# KUBODriver_MCU.net
KiCad netlist of a schematic drawn in Altium Designer
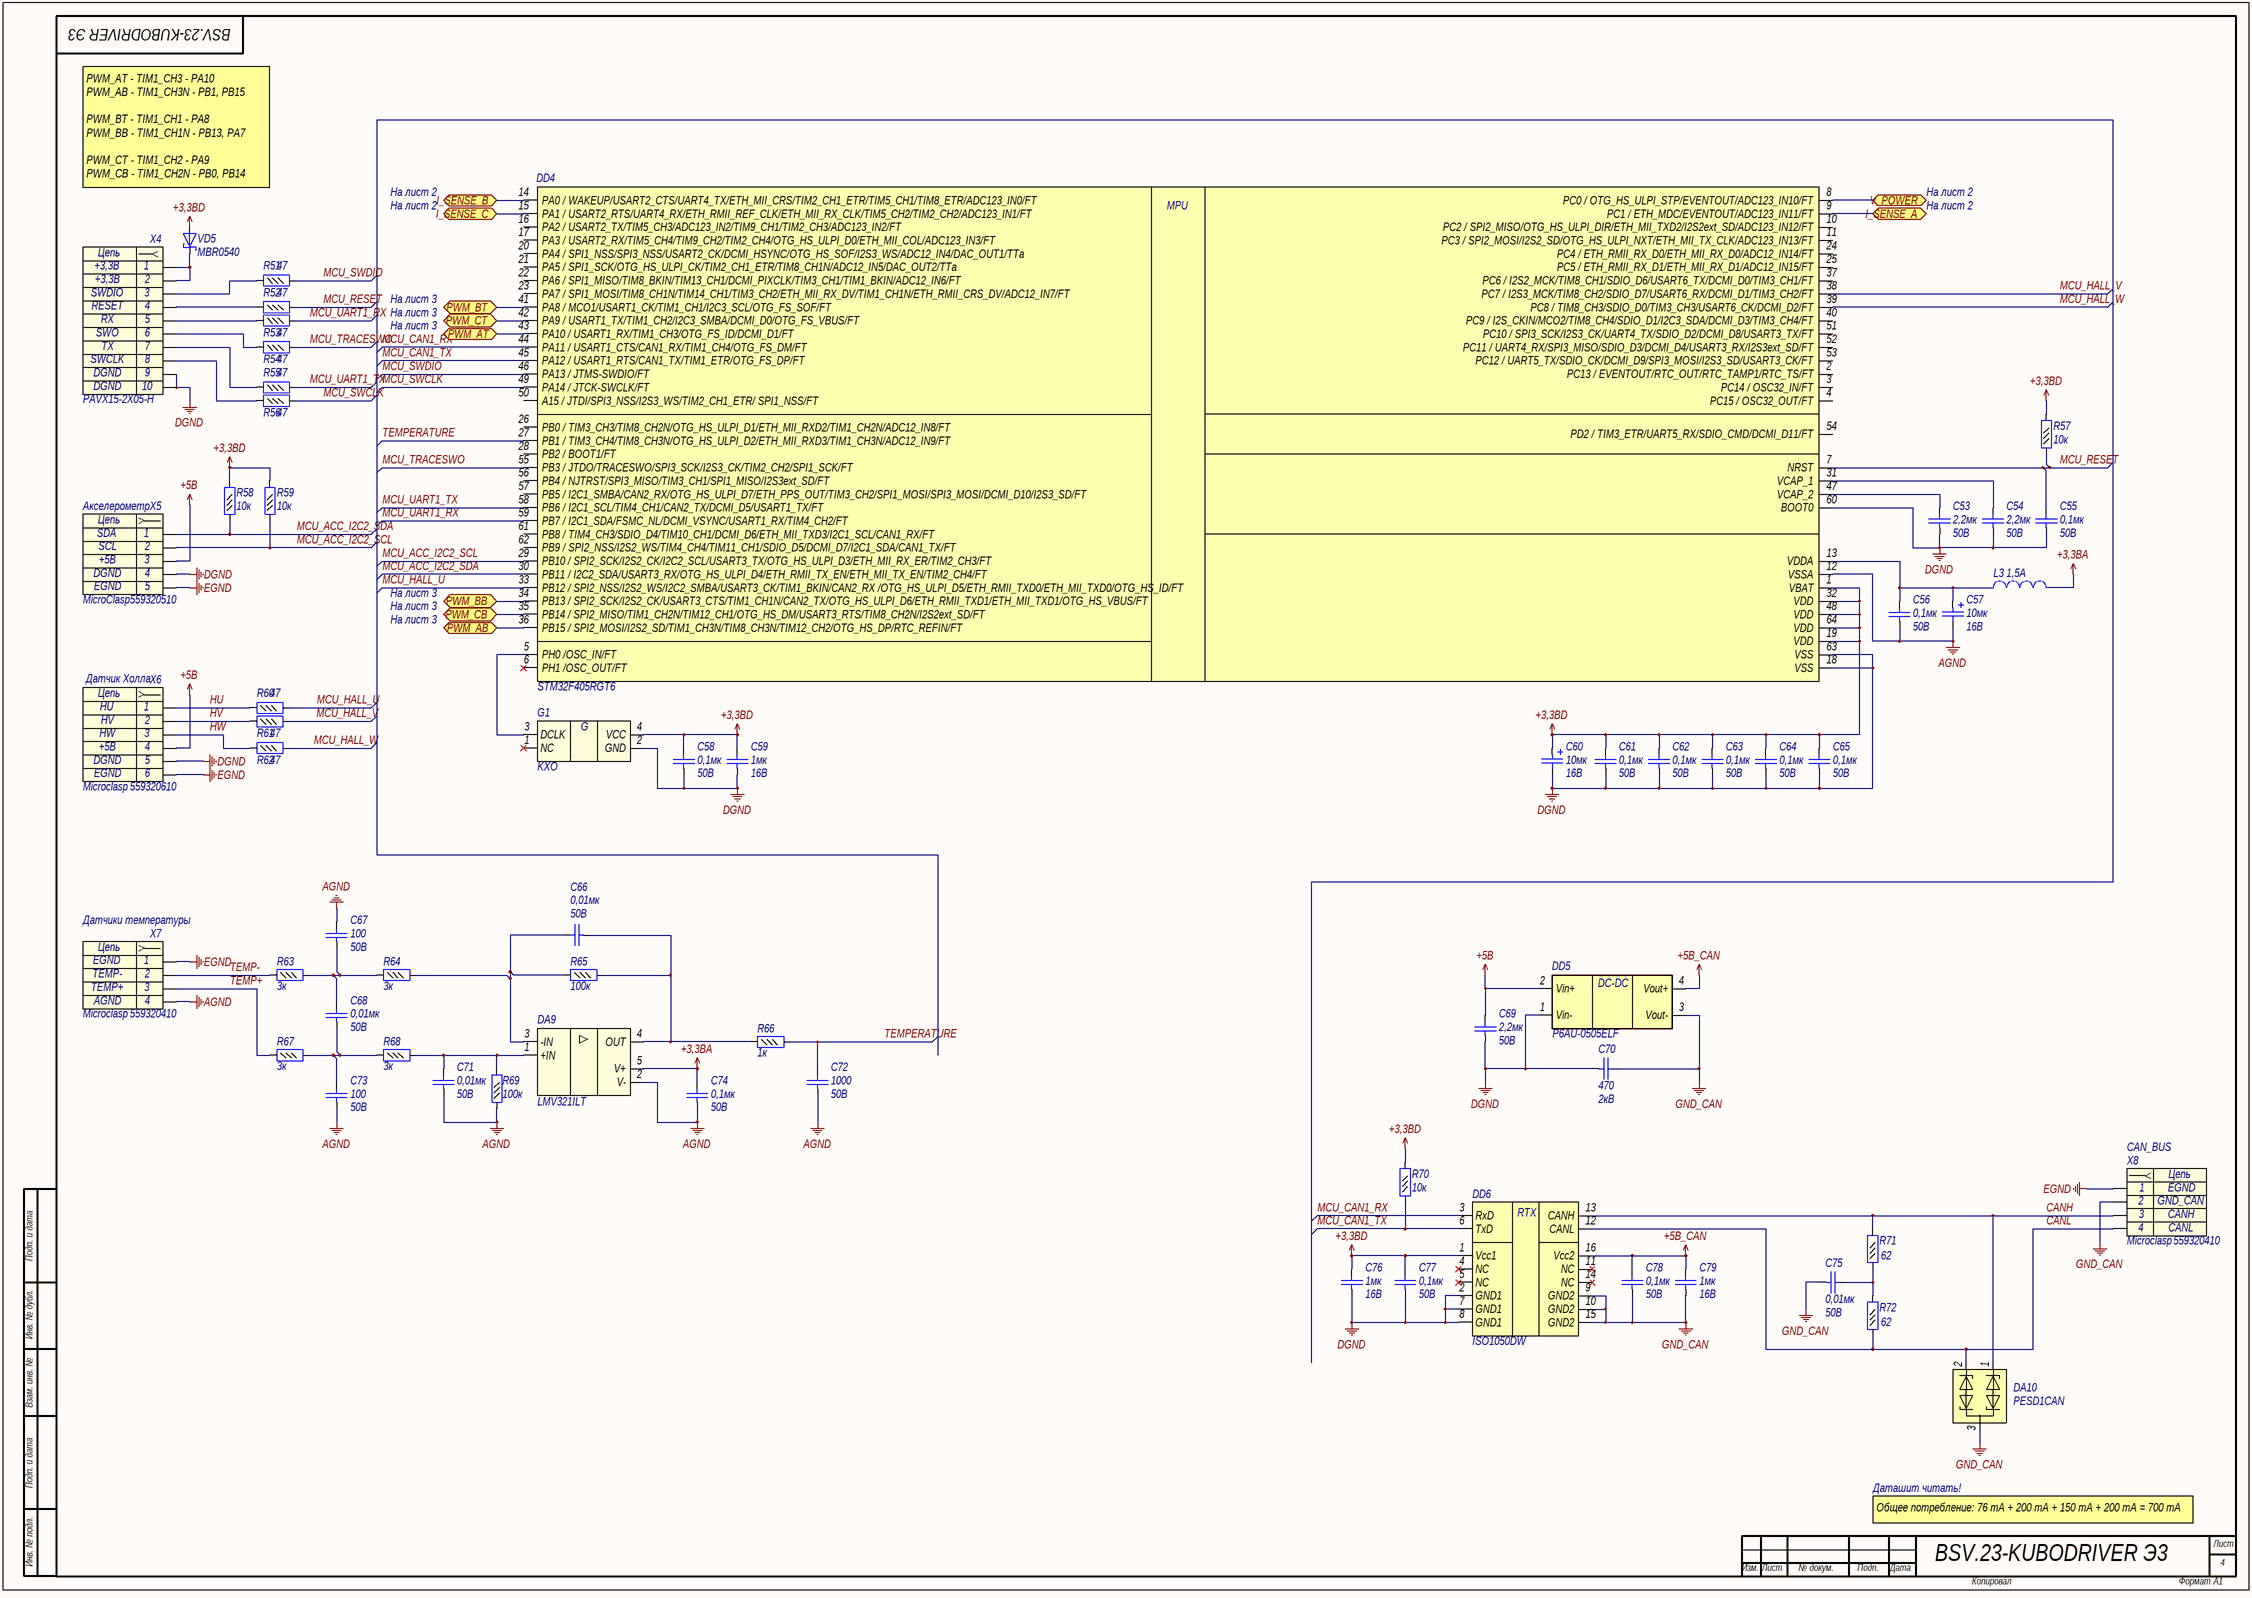
[diagram p0: KUBODriver_MCU.SchDoc]

(export (version "E")
  (design (tool "Eeschema 10.0.6"))
  (components
    (comp (ref "C53")
      (value "2,2мк")
      (footprint "C0603")
      (description "Конденсатор")
      (fields
        (field (name "VOLTAGE") "50B")
        (field (name "PART NUMBER") "GRM188R71A225KE15D")
        (field (name "Comment") "Capacitor")
      )
      (libsource (lib "MOP44") (part "Capacitor"))
    )
    (comp (ref "C54")
      (value "2,2мк")
      (footprint "C0603")
      (description "Конденсатор")
      (fields
        (field (name "VOLTAGE") "50B")
        (field (name "PART NUMBER") "GRM188R71A225KE15D")
        (field (name "Comment") "Capacitor")
      )
      (libsource (lib "MOP44") (part "Capacitor"))
    )
    (comp (ref "C55")
      (value "0,1мк")
      (footprint "C0402")
      (description "Конденсатор")
      (fields
        (field (name "VOLTAGE") "50В")
        (field (name "PART NUMBER") "GRM155R71H104KE14D ")
        (field (name "Comment") "Capacitor")
      )
      (libsource (lib "MOP44") (part "Capacitor"))
    )
    (comp (ref "C56")
      (value "0,1мк")
      (footprint "C0402")
      (description "Конденсатор")
      (fields
        (field (name "VOLTAGE") "50В")
        (field (name "PART NUMBER") "GRM155R71H104KE14D ")
        (field (name "Comment") "Capacitor")
      )
      (libsource (lib "MOP44") (part "Capacitor"))
    )
    (comp (ref "C57")
      (value "10мк")
      (footprint "TANTAL CASE A")
      (description "Конденсатор полярный")
      (fields
        (field (name "VOLTAGE") "16В")
        (field (name "PART NUMBER") "293D106X9016A2TE3")
        (field (name "Comment") "Capacitor_pol")
      )
      (libsource (lib "MOP44") (part "Capacitor_pol"))
    )
    (comp (ref "C58")
      (value "0,1мк")
      (footprint "C0402")
      (description "Конденсатор")
      (fields
        (field (name "VOLTAGE") "50В")
        (field (name "PART NUMBER") "GRM155R71H104KE14D ")
        (field (name "Comment") "Capacitor")
      )
      (libsource (lib "MOP44") (part "Capacitor"))
    )
    (comp (ref "C59")
      (value "1мк")
      (footprint "C0603")
      (description "Конденсатор")
      (fields
        (field (name "VOLTAGE") "16B")
        (field (name "PART NUMBER") "GRM188R71C105KA12D**")
        (field (name "Comment") "Capacitor")
      )
      (libsource (lib "MOP44") (part "Capacitor"))
    )
    (comp (ref "C60")
      (value "10мк")
      (footprint "TANTAL CASE A")
      (description "Конденсатор полярный")
      (fields
        (field (name "VOLTAGE") "16В")
        (field (name "PART NUMBER") "293D106X9016A2TE3")
        (field (name "Comment") "Capacitor_pol")
      )
      (libsource (lib "MOP44") (part "Capacitor_pol"))
    )
    (comp (ref "C61")
      (value "0,1мк")
      (footprint "C0402")
      (description "Конденсатор")
      (fields
        (field (name "VOLTAGE") "50В")
        (field (name "PART NUMBER") "GRM155R71H104KE14D ")
        (field (name "Comment") "Capacitor")
      )
      (libsource (lib "MOP44") (part "Capacitor"))
    )
    (comp (ref "C62")
      (value "0,1мк")
      (footprint "C0402")
      (description "Конденсатор")
      (fields
        (field (name "VOLTAGE") "50В")
        (field (name "PART NUMBER") "GRM155R71H104KE14D ")
        (field (name "Comment") "Capacitor")
      )
      (libsource (lib "MOP44") (part "Capacitor"))
    )
    (comp (ref "C63")
      (value "0,1мк")
      (footprint "C0402")
      (description "Конденсатор")
      (fields
        (field (name "VOLTAGE") "50В")
        (field (name "PART NUMBER") "GRM155R71H104KE14D ")
        (field (name "Comment") "Capacitor")
      )
      (libsource (lib "MOP44") (part "Capacitor"))
    )
    (comp (ref "C64")
      (value "0,1мк")
      (footprint "C0402")
      (description "Конденсатор")
      (fields
        (field (name "VOLTAGE") "50В")
        (field (name "PART NUMBER") "GRM155R71H104KE14D ")
        (field (name "Comment") "Capacitor")
      )
      (libsource (lib "MOP44") (part "Capacitor"))
    )
    (comp (ref "C65")
      (value "0,1мк")
      (footprint "C0402")
      (description "Конденсатор")
      (fields
        (field (name "VOLTAGE") "50В")
        (field (name "PART NUMBER") "GRM155R71H104KE14D ")
        (field (name "Comment") "Capacitor")
      )
      (libsource (lib "MOP44") (part "Capacitor"))
    )
    (comp (ref "C66")
      (value "0,01мк")
      (footprint "C0402")
      (description "Конденсатор")
      (fields
        (field (name "VOLTAGE") "50B")
        (field (name "PART NUMBER") "GRM155R71H103K")
        (field (name "Comment") "Capacitor")
      )
      (libsource (lib "MOP44") (part "Capacitor"))
    )
    (comp (ref "C67")
      (value "100")
      (footprint "C0402")
      (description "Конденсатор")
      (fields
        (field (name "VOLTAGE") "50B")
        (field (name "PART NUMBER") "GRM1535C1H101J")
        (field (name "Comment") "Capacitor")
      )
      (libsource (lib "MOP44") (part "Capacitor"))
    )
    (comp (ref "C68")
      (value "0,01мк")
      (footprint "C0402")
      (description "Конденсатор")
      (fields
        (field (name "VOLTAGE") "50B")
        (field (name "PART NUMBER") "GRM155R71H103K")
        (field (name "Comment") "Capacitor")
      )
      (libsource (lib "MOP44") (part "Capacitor"))
    )
    (comp (ref "C69")
      (value "2,2мк")
      (footprint "C0603")
      (description "Конденсатор")
      (fields
        (field (name "VOLTAGE") "50B")
        (field (name "PART NUMBER") "GRM188R71A225KE15D")
        (field (name "Comment") "Capacitor")
      )
      (libsource (lib "MOP44") (part "Capacitor"))
    )
    (comp (ref "C70")
      (value "470")
      (footprint "C1206")
      (description "Конденсатор")
      (fields
        (field (name "VOLTAGE") "2кВ")
        (field (name "PART NUMBER") "CC1206KKX7RDBB471 ")
        (field (name "Comment") "Capacitor")
      )
      (libsource (lib "MOP44") (part "Capacitor"))
    )
    (comp (ref "C71")
      (value "0,01мк")
      (footprint "C0402")
      (description "Конденсатор")
      (fields
        (field (name "VOLTAGE") "50B")
        (field (name "PART NUMBER") "GRM155R71H103K")
        (field (name "Comment") "Capacitor")
      )
      (libsource (lib "MOP44") (part "Capacitor"))
    )
    (comp (ref "C72")
      (value "1000")
      (footprint "C0402")
      (description "Конденсатор")
      (fields
        (field (name "VOLTAGE") "50B")
        (field (name "PART NUMBER") "GRM1555C1H102J")
        (field (name "Comment") "Capacitor")
      )
      (libsource (lib "MOP44") (part "Capacitor"))
    )
    (comp (ref "C73")
      (value "100")
      (footprint "C0402")
      (description "Конденсатор")
      (fields
        (field (name "VOLTAGE") "50B")
        (field (name "PART NUMBER") "GRM1535C1H101J")
        (field (name "Comment") "Capacitor")
      )
      (libsource (lib "MOP44") (part "Capacitor"))
    )
    (comp (ref "C74")
      (value "0,1мк")
      (footprint "C0402")
      (description "Конденсатор")
      (fields
        (field (name "VOLTAGE") "50В")
        (field (name "PART NUMBER") "GRM155R71H104KE14D ")
        (field (name "Comment") "Capacitor")
      )
      (libsource (lib "MOP44") (part "Capacitor"))
    )
    (comp (ref "C75")
      (value "0,01мк")
      (footprint "C0402")
      (description "Конденсатор")
      (fields
        (field (name "VOLTAGE") "50B")
        (field (name "PART NUMBER") "GRM155R71H103K")
        (field (name "Comment") "Capacitor")
      )
      (libsource (lib "MOP44") (part "Capacitor"))
    )
    (comp (ref "C76")
      (value "1мк")
      (footprint "C0603")
      (description "Конденсатор")
      (fields
        (field (name "VOLTAGE") "16B")
        (field (name "PART NUMBER") "GRM188R71C105KA12D**")
        (field (name "Comment") "Capacitor")
      )
      (libsource (lib "MOP44") (part "Capacitor"))
    )
    (comp (ref "C77")
      (value "0,1мк")
      (footprint "C0402")
      (description "Конденсатор")
      (fields
        (field (name "VOLTAGE") "50В")
        (field (name "PART NUMBER") "GRM155R71H104KE14D ")
        (field (name "Comment") "Capacitor")
      )
      (libsource (lib "MOP44") (part "Capacitor"))
    )
    (comp (ref "C78")
      (value "0,1мк")
      (footprint "C0402")
      (description "Конденсатор")
      (fields
        (field (name "VOLTAGE") "50В")
        (field (name "PART NUMBER") "GRM155R71H104KE14D ")
        (field (name "Comment") "Capacitor")
      )
      (libsource (lib "MOP44") (part "Capacitor"))
    )
    (comp (ref "C79")
      (value "1мк")
      (footprint "C0603")
      (description "Конденсатор")
      (fields
        (field (name "VOLTAGE") "16B")
        (field (name "PART NUMBER") "GRM188R71C105KA12D**")
        (field (name "Comment") "Capacitor")
      )
      (libsource (lib "MOP44") (part "Capacitor"))
    )
    (comp (ref "DA9")
      (value "LMV321ILT")
      (footprint "SOT23-5")
      (description "HIGH-DRIVE OPERATIONAL AMPLIFIERS WITH SHUTDOWN")
      (libsource (lib "MOP44") (part "LMV321ILT"))
    )
    (comp (ref "DA10")
      (value "PESD")
      (footprint "SOT23-3")
      (description "TVS")
      (fields (field (name "PART NUMBER") "PESD1CAN"))
      (libsource (lib "MOP44") (part "PESD"))
    )
    (comp (ref "DD4")
      (value "STM32F405RGT6")
      (footprint "LQFP64")
      (libsource (lib "MOP44") (part "STM32F405RGT6"))
    )
    (comp (ref "DD5")
      (value "P6AU-xxxxELF")
      (footprint "SIP4")
      (description "DC/DC преобразователь")
      (fields (field (name "PART NUMBER") "P6AU-0505ELF") (field (name "MANUFACTURER") "PEAK Electronics"))
      (libsource (lib "MOP44") (part "P6AU-xxxxELF"))
    )
    (comp (ref "DD6")
      (value "~")
      (footprint "SO16")
      (description "Isolated CAN Transceiver")
      (fields (field (name "PART NUMBER") "ISO1050DW"))
      (libsource (lib "MOP44") (part "ISO1050DW"))
    )
    (comp (ref "G1")
      (value "KXO")
      (footprint "QSMD7x5.2x1.8")
      (description "Кварц. генер. 32.768 МГц (HCMOS/TTL)")
      (fields (field (name "PART NUMBER") "KXO-V97"))
      (libsource (lib "MOP44") (part "KXO"))
    )
    (comp (ref "L3")
      (value "Inductor")
      (footprint "L0603")
      (description "EMI Suppression Filter")
      (fields (field (name "RATED CURRENT") "1,5A") (field (name "PART NUMBER") "BLM18PG181SN1D"))
      (libsource (lib "MOP44") (part "Inductor"))
    )
    (comp (ref "R51")
      (value "47")
      (footprint "R0402")
      (description "Резистор")
      (fields (field (name "PART NUMBER") "RC0402FR-0747RL") (field (name "POWER") "0,062Вт"))
      (libsource (lib "MOP44") (part "Resistor_0,062Вт"))
    )
    (comp (ref "R52")
      (value "47")
      (footprint "R0402")
      (description "Резистор")
      (fields (field (name "PART NUMBER") "RC0402FR-0747RL") (field (name "POWER") "0,062Вт"))
      (libsource (lib "MOP44") (part "Resistor_0,062Вт"))
    )
    (comp (ref "R53")
      (value "47")
      (footprint "R0402")
      (description "Резистор")
      (fields (field (name "PART NUMBER") "RC0402FR-0747RL") (field (name "POWER") "0,062Вт"))
      (libsource (lib "MOP44") (part "Resistor_0,062Вт"))
    )
    (comp (ref "R54")
      (value "47")
      (footprint "R0402")
      (description "Резистор")
      (fields (field (name "PART NUMBER") "RC0402FR-0747RL") (field (name "POWER") "0,062Вт"))
      (libsource (lib "MOP44") (part "Resistor_0,062Вт"))
    )
    (comp (ref "R55")
      (value "47")
      (footprint "R0402")
      (description "Резистор")
      (fields (field (name "PART NUMBER") "RC0402FR-0747RL") (field (name "POWER") "0,062Вт"))
      (libsource (lib "MOP44") (part "Resistor_0,062Вт"))
    )
    (comp (ref "R56")
      (value "47")
      (footprint "R0402")
      (description "Резистор")
      (fields (field (name "PART NUMBER") "RC0402FR-0747RL") (field (name "POWER") "0,062Вт"))
      (libsource (lib "MOP44") (part "Resistor_0,062Вт"))
    )
    (comp (ref "R57")
      (value "10к")
      (footprint "R0402")
      (description "Резистор")
      (fields (field (name "PART NUMBER") "RC0402FR-0710KL") (field (name "POWER") "0,062Вт"))
      (libsource (lib "") (part "Resistor_0,062Вт_1"))
    )
    (comp (ref "R58")
      (value "10к")
      (footprint "R0402")
      (description "Резистор")
      (fields (field (name "PART NUMBER") "RC0402FR-0710KL") (field (name "POWER") "0,062Вт"))
      (libsource (lib "") (part "Resistor_0,062Вт_1"))
    )
    (comp (ref "R59")
      (value "10к")
      (footprint "R0402")
      (description "Резистор")
      (fields (field (name "PART NUMBER") "RC0402FR-0710KL") (field (name "POWER") "0,062Вт"))
      (libsource (lib "") (part "Resistor_0,062Вт_1"))
    )
    (comp (ref "R60")
      (value "47")
      (footprint "R0402")
      (description "Резистор")
      (fields (field (name "PART NUMBER") "RC0402FR-0747RL") (field (name "POWER") "0,062Вт"))
      (libsource (lib "MOP44") (part "Resistor_0,062Вт"))
    )
    (comp (ref "R61")
      (value "47")
      (footprint "R0402")
      (description "Резистор")
      (fields (field (name "PART NUMBER") "RC0402FR-0747RL") (field (name "POWER") "0,062Вт"))
      (libsource (lib "MOP44") (part "Resistor_0,062Вт"))
    )
    (comp (ref "R62")
      (value "47")
      (footprint "R0402")
      (description "Резистор")
      (fields (field (name "PART NUMBER") "RC0402FR-0747RL") (field (name "POWER") "0,062Вт"))
      (libsource (lib "MOP44") (part "Resistor_0,062Вт"))
    )
    (comp (ref "R63")
      (value "3к")
      (footprint "R0402")
      (description "Резистор")
      (fields (field (name "PART NUMBER") "RC0402FR-073KL") (field (name "POWER") "0,062Вт"))
      (libsource (lib "MOP44") (part "Resistor_0,062Вт"))
    )
    (comp (ref "R64")
      (value "3к")
      (footprint "R0402")
      (description "Резистор")
      (fields (field (name "PART NUMBER") "RC0402FR-073KL") (field (name "POWER") "0,062Вт"))
      (libsource (lib "MOP44") (part "Resistor_0,062Вт"))
    )
    (comp (ref "R65")
      (value "100к")
      (footprint "R0402")
      (description "Резистор")
      (fields (field (name "PART NUMBER") "RC0402FR-07100KL") (field (name "POWER") "0,062Вт"))
      (libsource (lib "MOP44") (part "Resistor_0,062Вт"))
    )
    (comp (ref "R66")
      (value "1к")
      (footprint "R0402")
      (description "Резистор")
      (fields (field (name "PART NUMBER") "RC0402FR-071KL") (field (name "POWER") "0,062Вт"))
      (libsource (lib "MOP44") (part "Resistor_0,062Вт"))
    )
    (comp (ref "R67")
      (value "3к")
      (footprint "R0402")
      (description "Резистор")
      (fields (field (name "PART NUMBER") "RC0402FR-073KL") (field (name "POWER") "0,062Вт"))
      (libsource (lib "MOP44") (part "Resistor_0,062Вт"))
    )
    (comp (ref "R68")
      (value "3к")
      (footprint "R0402")
      (description "Резистор")
      (fields (field (name "PART NUMBER") "RC0402FR-073KL") (field (name "POWER") "0,062Вт"))
      (libsource (lib "MOP44") (part "Resistor_0,062Вт"))
    )
    (comp (ref "R69")
      (value "100к")
      (footprint "R0402")
      (description "Резистор")
      (fields (field (name "PART NUMBER") "RC0402FR-07100KL") (field (name "POWER") "0,062Вт"))
      (libsource (lib "") (part "Resistor_0,062Вт_1"))
    )
    (comp (ref "R70")
      (value "10к")
      (footprint "R0402")
      (description "Резистор")
      (fields (field (name "PART NUMBER") "RC0402FR-0710KL") (field (name "POWER") "0,062Вт"))
      (libsource (lib "") (part "Resistor_0,062Вт_1"))
    )
    (comp (ref "R71")
      (value "62")
      (footprint "R0402")
      (description "Резистор")
      (fields (field (name "PART NUMBER") "RC0402FR-0762RL") (field (name "POWER") "0,062Вт"))
      (libsource (lib "") (part "Resistor_0,062Вт_1"))
    )
    (comp (ref "R72")
      (value "62")
      (footprint "R0402")
      (description "Резистор")
      (fields (field (name "PART NUMBER") "RC0402FR-0762RL") (field (name "POWER") "0,062Вт"))
      (libsource (lib "") (part "Resistor_0,062Вт_1"))
    )
    (comp (ref "VD5")
      (value "DiodeSchottky")
      (footprint "SOD-123")
      (description "Диод Шоттки")
      (fields (field (name "PART NUMBER") "MBR0540"))
      (libsource (lib "MOP44") (part "DiodeSchottky"))
    )
    (comp (ref "X4")
      (value "Header_10_sct")
      (footprint "PAVX15-2X05-H")
      (description "Разъем - 10 конт. розетка")
      (fields (field (name "PART NUMBER") "PAVX15-2X05-H"))
      (libsource (lib "MOP44") (part "Header_10_sct"))
    )
    (comp (ref "X5")
      (value "Акселерометр")
      (footprint "MOLEX_559320510")
      (description "Разъем - 5 конт. розетка")
      (fields (field (name "PART NAME") "MicroClasp") (field (name "PART NUMBER") "559320510"))
      (libsource (lib "MOP44") (part "Header_5_sct"))
    )
    (comp (ref "X6")
      (value "Датчик Холла")
      (footprint "MOLEX_559320610")
      (description "Разъем - 6 конт. розетка")
      (fields (field (name "PART NUMBER") "559320610"))
      (libsource (lib "MOP44") (part "Header_6_sct"))
    )
    (comp (ref "X7")
      (value "Датчики температуры")
      (footprint "MOLEX_559320410")
      (description "Разъем - 4 конт. розетка")
      (fields (field (name "PART NUMBER") "559320410"))
      (libsource (lib "") (part "Header_4_sct_1"))
    )
    (comp (ref "X8")
      (value "CAN_BUS")
      (footprint "MOLEX_559320410")
      (description "Разъем - 4 конт. розетка")
      (fields (field (name "PART NUMBER") "559320410"))
      (libsource (lib "MOP44") (part "Header_4_sct"))
    )
  )
  (nets
    (net (code "1") (name "+3,3BA") (class "Default")
      (node (ref "C74") (pin "2") (pinfunction "2_2") (pintype "passive"))
      (node (ref "DA9") (pin "5") (pinfunction "V+_5") (pintype "passive"))
      (node (ref "L3") (pin "2") (pinfunction "2_2") (pintype "passive"))
    )
    (net (code "2") (name "+3,3BD") (class "Default")
      (node (ref "C58") (pin "2") (pinfunction "2_2") (pintype "passive"))
      (node (ref "C59") (pin "2") (pinfunction "2_2") (pintype "passive"))
      (node (ref "C60") (pin "1") (pinfunction "1_1") (pintype "passive"))
      (node (ref "C61") (pin "2") (pinfunction "2_2") (pintype "passive"))
      (node (ref "C62") (pin "2") (pinfunction "2_2") (pintype "passive"))
      (node (ref "C63") (pin "2") (pinfunction "2_2") (pintype "passive"))
      (node (ref "C64") (pin "2") (pinfunction "2_2") (pintype "passive"))
      (node (ref "C65") (pin "2") (pinfunction "2_2") (pintype "passive"))
      (node (ref "C76") (pin "2") (pinfunction "2_2") (pintype "passive"))
      (node (ref "C77") (pin "2") (pinfunction "2_2") (pintype "passive"))
      (node (ref "DD4") (pin "1") (pinfunction "VBAT_1") (pintype "passive"))
      (node (ref "DD4") (pin "19") (pinfunction "VDD_19") (pintype "passive"))
      (node (ref "DD4") (pin "32") (pinfunction "VDD_32") (pintype "passive"))
      (node (ref "DD4") (pin "48") (pinfunction "VDD_48") (pintype "passive"))
      (node (ref "DD4") (pin "64") (pinfunction "VDD_64") (pintype "passive"))
      (node (ref "DD6") (pin "1") (pinfunction "Vcc1_1") (pintype "passive"))
      (node (ref "G1") (pin "4") (pinfunction "VCC_4") (pintype "power_in"))
      (node (ref "R57") (pin "2") (pinfunction "2_2") (pintype "passive"))
      (node (ref "R58") (pin "2") (pinfunction "2_2") (pintype "passive"))
      (node (ref "R59") (pin "2") (pinfunction "2_2") (pintype "passive"))
      (node (ref "R70") (pin "2") (pinfunction "2_2") (pintype "passive"))
      (node (ref "VD5") (pin "2") (pinfunction "A_2") (pintype "passive"))
    )
    (net (code "3") (name "+5B") (class "Default")
      (node (ref "C69") (pin "2") (pinfunction "2_2") (pintype "passive"))
      (node (ref "DD5") (pin "2") (pinfunction "Vin+_2") (pintype "passive"))
      (node (ref "X5") (pin "3") (pinfunction "3_3") (pintype "passive"))
      (node (ref "X6") (pin "4") (pinfunction "4_4") (pintype "passive"))
    )
    (net (code "4") (name "+5B_CAN") (class "Default")
      (node (ref "C78") (pin "2") (pinfunction "2_2") (pintype "passive"))
      (node (ref "C79") (pin "2") (pinfunction "2_2") (pintype "passive"))
      (node (ref "DD5") (pin "4") (pinfunction "Vout+_4") (pintype "passive"))
      (node (ref "DD6") (pin "16") (pinfunction "Vcc2_16") (pintype "passive"))
    )
    (net (code "5") (name "/CANH") (class "Default")
      (node (ref "DA10") (pin "1") (pintype "passive"))
      (node (ref "DD6") (pin "13") (pinfunction "CANH_13") (pintype "passive"))
      (node (ref "R71") (pin "2") (pinfunction "2_2") (pintype "passive"))
      (node (ref "X8") (pin "3") (pinfunction "3_3") (pintype "passive"))
    )
    (net (code "6") (name "/CANL") (class "Default")
      (node (ref "DA10") (pin "2") (pinfunction "1_2") (pintype "passive"))
      (node (ref "DD6") (pin "12") (pinfunction "CANL_12") (pintype "passive"))
      (node (ref "R72") (pin "1") (pinfunction "1_1") (pintype "passive"))
      (node (ref "X8") (pin "4") (pinfunction "4_4") (pintype "passive"))
    )
    (net (code "7") (name "/HU") (class "Default")
      (node (ref "R60") (pin "1") (pinfunction "1_1") (pintype "passive"))
      (node (ref "X6") (pin "1") (pinfunction "1_1") (pintype "passive"))
    )
    (net (code "8") (name "/HV") (class "Default")
      (node (ref "R61") (pin "1") (pinfunction "1_1") (pintype "passive"))
      (node (ref "X6") (pin "2") (pinfunction "2_2") (pintype "passive"))
    )
    (net (code "9") (name "/HW") (class "Default")
      (node (ref "R62") (pin "1") (pinfunction "1_1") (pintype "passive"))
      (node (ref "X6") (pin "3") (pinfunction "3_3") (pintype "passive"))
    )
    (net (code "10") (name "/I_SENSE_A") (class "Default")
      (node (ref "DD4") (pin "9") (pinfunction "PC1_/_ETH_MDC/EVENTOUT/ADC123_IN11/FT_9") (pintype "passive"))
    )
    (net (code "11") (name "/I_SENSE_B") (class "Default")
      (node (ref "DD4") (pin "14") (pinfunction "PA0_/_WAKEUP/USART2_CTS/UART4_TX/ETH_MII_CRS/TIM2_CH1_ETR/TIM5_CH1/TIM8_ETR/ADC123_IN0/FT_14") (pintype "passive"))
    )
    (net (code "12") (name "/I_SENSE_C") (class "Default")
      (node (ref "DD4") (pin "15") (pinfunction "PA1_/_USART2_RTS/UART4_RX/ETH_RMII_REF_CLK/ETH_MII_RX_CLK/TIM5_CH2/TIM2_CH2/ADC123_IN1/FT_15") (pintype "passive"))
    )
    (net (code "13") (name "/MCU_ACC_I2C2_SCL") (class "Default")
      (node (ref "DD4") (pin "29") (pinfunction "PB10_/_SPI2_SCK/I2S2_CK/I2C2_SCL/USART3_TX/OTG_HS_ULPI_D3/ETH_MII_RX_ER/TIM2_CH3/FT_29") (pintype "passive"))
      (node (ref "R59") (pin "1") (pinfunction "1_1") (pintype "passive"))
      (node (ref "X5") (pin "2") (pinfunction "2_2") (pintype "passive"))
    )
    (net (code "14") (name "/MCU_ACC_I2C2_SDA") (class "Default")
      (node (ref "DD4") (pin "30") (pinfunction "PB11_/_I2C2_SDA/USART3_RX/OTG_HS_ULPI_D4/ETH_RMII_TX_EN/ETH_MII_TX_EN/TIM2_CH4/FT_30") (pintype "passive"))
      (node (ref "R58") (pin "1") (pinfunction "1_1") (pintype "passive"))
      (node (ref "X5") (pin "1") (pinfunction "1_1") (pintype "passive"))
    )
    (net (code "15") (name "/MCU_CAN1_RX") (class "Default")
      (node (ref "DD4") (pin "44") (pinfunction "PA11_/_USART1_CTS/CAN1_RX/TIM1_CH4/OTG_FS_DM/FT_44") (pintype "passive"))
      (node (ref "DD6") (pin "3") (pinfunction "RxD_3") (pintype "passive"))
    )
    (net (code "16") (name "/MCU_CAN1_TX") (class "Default")
      (node (ref "DD4") (pin "45") (pinfunction "PA12_/_USART1_RTS/CAN1_TX/TIM1_ETR/OTG_FS_DP/FT_45") (pintype "passive"))
      (node (ref "DD6") (pin "6") (pinfunction "TxD_6") (pintype "passive"))
      (node (ref "R70") (pin "1") (pinfunction "1_1") (pintype "passive"))
    )
    (net (code "17") (name "/MCU_HALL_U") (class "Default")
      (node (ref "DD4") (pin "33") (pinfunction "PB12_/_SPI2_NSS/I2S2_WS/I2C2_SMBA/USART3_CK/TIM1_BKIN/CAN2_RX_/OTG_HS_ULPI_D5/ETH_RMII_TXD0/ETH_MII_TXD0/OTG_HS_ID/FT_33") (pintype "passive"))
      (node (ref "R60") (pin "2") (pinfunction "2_2") (pintype "passive"))
    )
    (net (code "18") (name "/MCU_HALL_V") (class "Default")
      (node (ref "DD4") (pin "38") (pinfunction "PC7_/_I2S3_MCK/TIM8_CH2/SDIO_D7/USART6_RX/DCMI_D1/TIM3_CH2/FT_38") (pintype "passive"))
      (node (ref "R61") (pin "2") (pinfunction "2_2") (pintype "passive"))
    )
    (net (code "19") (name "/MCU_HALL_W") (class "Default")
      (node (ref "DD4") (pin "39") (pinfunction "PC8_/_TIM8_CH3/SDIO_D0/TIM3_CH3/USART6_CK/DCMI_D2/FT_39") (pintype "passive"))
      (node (ref "R62") (pin "2") (pinfunction "2_2") (pintype "passive"))
    )
    (net (code "20") (name "/MCU_RESET") (class "Default")
      (node (ref "C55") (pin "2") (pinfunction "2_2") (pintype "passive"))
      (node (ref "DD4") (pin "7") (pinfunction "NRST_7") (pintype "passive"))
      (node (ref "R52") (pin "2") (pinfunction "2_2") (pintype "passive"))
      (node (ref "R57") (pin "1") (pinfunction "1_1") (pintype "passive"))
    )
    (net (code "21") (name "/MCU_SWCLK") (class "Default")
      (node (ref "DD4") (pin "49") (pinfunction "PA14_/_JTCK-SWCLK/FT_49") (pintype "passive"))
      (node (ref "R56") (pin "2") (pinfunction "2_2") (pintype "passive"))
    )
    (net (code "22") (name "/MCU_SWDIO") (class "Default")
      (node (ref "DD4") (pin "46") (pinfunction "PA13_/_JTMS-SWDIO/FT_46") (pintype "passive"))
      (node (ref "R51") (pin "2") (pinfunction "2_2") (pintype "passive"))
    )
    (net (code "23") (name "/MCU_TRACESWO") (class "Default")
      (node (ref "DD4") (pin "55") (pinfunction "PB3_/_JTDO/TRACESWO/SPI3_SCK/I2S3_CK/TIM2_CH2/SPI1_SCK/FT_55") (pintype "passive"))
      (node (ref "R54") (pin "2") (pinfunction "2_2") (pintype "passive"))
    )
    (net (code "24") (name "/MCU_UART1_RX") (class "Default")
      (node (ref "DD4") (pin "59") (pinfunction "PB7_/_I2C1_SDA/FSMC_NL/DCMI_VSYNC/USART1_RX/TIM4_CH2/FT_59") (pintype "passive"))
      (node (ref "R53") (pin "2") (pinfunction "2_2") (pintype "passive"))
    )
    (net (code "25") (name "/MCU_UART1_TX") (class "Default")
      (node (ref "DD4") (pin "58") (pinfunction "PB6_/_I2C1_SCL/TIM4_CH1/CAN2_TX/DCMI_D5/USART1_TX/FT_58") (pintype "passive"))
      (node (ref "R55") (pin "2") (pinfunction "2_2") (pintype "passive"))
    )
    (net (code "26") (name "/PWM_AB") (class "Default")
      (node (ref "DD4") (pin "36") (pinfunction "PB15_/_SPI2_MOSI/I2S2_SD/TIM1_CH3N/TIM8_CH3N/TIM12_CH2/OTG_HS_DP/RTC_REFIN/FT_36") (pintype "passive"))
    )
    (net (code "27") (name "/PWM_AT") (class "Default")
      (node (ref "DD4") (pin "43") (pinfunction "PA10_/_USART1_RX/TIM1_CH3/OTG_FS_ID/DCMI_D1/FT_43") (pintype "passive"))
    )
    (net (code "28") (name "/PWM_BB") (class "Default")
      (node (ref "DD4") (pin "34") (pinfunction "PB13_/_SPI2_SCK/I2S2_CK/USART3_CTS/TIM1_CH1N/CAN2_TX/OTG_HS_ULPI_D6/ETH_RMII_TXD1/ETH_MII_TXD1/OTG_HS_VBUS/FT_34") (pintype "passive"))
    )
    (net (code "29") (name "/PWM_BT") (class "Default")
      (node (ref "DD4") (pin "41") (pinfunction "PA8_/_MCO1/USART1_CK/TIM1_CH1/I2C3_SCL/OTG_FS_SOF/FT_41") (pintype "passive"))
    )
    (net (code "30") (name "/PWM_CB") (class "Default")
      (node (ref "DD4") (pin "35") (pinfunction "PB14_/_SPI2_MISO/TIM1_CH2N/TIM12_CH1/OTG_HS_DM/USART3_RTS/TIM8_CH2N/I2S2ext_SD/FT_35") (pintype "passive"))
    )
    (net (code "31") (name "/PWM_CT") (class "Default")
      (node (ref "DD4") (pin "42") (pinfunction "PA9_/_USART1_TX/TIM1_CH2/I2C3_SMBA/DCMI_D0/OTG_FS_VBUS/FT_42") (pintype "passive"))
    )
    (net (code "32") (name "/TEMP+") (class "Default")
      (node (ref "R67") (pin "1") (pinfunction "1_1") (pintype "passive"))
      (node (ref "X7") (pin "3") (pinfunction "3_3") (pintype "passive"))
    )
    (net (code "33") (name "/TEMP-") (class "Default")
      (node (ref "R63") (pin "1") (pinfunction "1_1") (pintype "passive"))
      (node (ref "X7") (pin "2") (pinfunction "2_2") (pintype "passive"))
    )
    (net (code "34") (name "/TEMPERATURE") (class "Default")
      (node (ref "C72") (pin "2") (pinfunction "2_2") (pintype "passive"))
      (node (ref "DD4") (pin "27") (pinfunction "PB1_/_TIM3_CH4/TIM8_CH3N/OTG_HS_ULPI_D2/ETH_MII_RXD3/TIM1_CH3N/ADC12_IN9/FT_27") (pintype "passive"))
      (node (ref "R66") (pin "2") (pinfunction "2_2") (pintype "passive"))
    )
    (net (code "35") (name "/V_POWER") (class "Default")
      (node (ref "DD4") (pin "8") (pinfunction "PC0_/_OTG_HS_ULPI_STP/EVENTOUT/ADC123_IN10/FT_8") (pintype "passive"))
    )
    (net (code "36") (name "AGND") (class "Default")
      (node (ref "C56") (pin "1") (pinfunction "1_1") (pintype "passive"))
      (node (ref "C57") (pin "2") (pinfunction "2_2") (pintype "passive"))
      (node (ref "C67") (pin "2") (pinfunction "2_2") (pintype "passive"))
      (node (ref "C71") (pin "1") (pinfunction "1_1") (pintype "passive"))
      (node (ref "C72") (pin "1") (pinfunction "1_1") (pintype "passive"))
      (node (ref "C73") (pin "1") (pinfunction "1_1") (pintype "passive"))
      (node (ref "C74") (pin "1") (pinfunction "1_1") (pintype "passive"))
      (node (ref "DA9") (pin "2") (pinfunction "V-_2") (pintype "passive"))
      (node (ref "DD4") (pin "12") (pinfunction "VSSA_12") (pintype "passive"))
      (node (ref "R69") (pin "1") (pinfunction "1_1") (pintype "passive"))
      (node (ref "X7") (pin "4") (pinfunction "4_4") (pintype "passive"))
    )
    (net (code "37") (name "DGND") (class "Default")
      (node (ref "C53") (pin "1") (pinfunction "1_1") (pintype "passive"))
      (node (ref "C54") (pin "1") (pinfunction "1_1") (pintype "passive"))
      (node (ref "C55") (pin "1") (pinfunction "1_1") (pintype "passive"))
      (node (ref "C58") (pin "1") (pinfunction "1_1") (pintype "passive"))
      (node (ref "C59") (pin "1") (pinfunction "1_1") (pintype "passive"))
      (node (ref "C60") (pin "2") (pinfunction "2_2") (pintype "passive"))
      (node (ref "C61") (pin "1") (pinfunction "1_1") (pintype "passive"))
      (node (ref "C62") (pin "1") (pinfunction "1_1") (pintype "passive"))
      (node (ref "C63") (pin "1") (pinfunction "1_1") (pintype "passive"))
      (node (ref "C64") (pin "1") (pinfunction "1_1") (pintype "passive"))
      (node (ref "C65") (pin "1") (pinfunction "1_1") (pintype "passive"))
      (node (ref "C69") (pin "1") (pinfunction "1_1") (pintype "passive"))
      (node (ref "C70") (pin "1") (pinfunction "1_1") (pintype "passive"))
      (node (ref "C76") (pin "1") (pinfunction "1_1") (pintype "passive"))
      (node (ref "C77") (pin "1") (pinfunction "1_1") (pintype "passive"))
      (node (ref "DD4") (pin "18") (pinfunction "VSS_18") (pintype "passive"))
      (node (ref "DD4") (pin "60") (pinfunction "BOOT0_60") (pintype "passive"))
      (node (ref "DD4") (pin "63") (pinfunction "VSS_63") (pintype "passive"))
      (node (ref "DD5") (pin "1") (pinfunction "Vin-_1") (pintype "passive"))
      (node (ref "DD6") (pin "2") (pinfunction "GND1_2") (pintype "passive"))
      (node (ref "DD6") (pin "7") (pinfunction "GND1_7") (pintype "passive"))
      (node (ref "DD6") (pin "8") (pinfunction "GND1_8") (pintype "passive"))
      (node (ref "G1") (pin "2") (pinfunction "GND_2") (pintype "power_in"))
      (node (ref "X4") (pin "10") (pinfunction "10_10") (pintype "passive"))
      (node (ref "X4") (pin "9") (pinfunction "9_9") (pintype "passive"))
      (node (ref "X5") (pin "4") (pinfunction "4_4") (pintype "passive"))
      (node (ref "X6") (pin "5") (pinfunction "5_5") (pintype "passive"))
    )
    (net (code "38") (name "EGND") (class "Default")
      (node (ref "X5") (pin "5") (pinfunction "5_5") (pintype "passive"))
      (node (ref "X6") (pin "6") (pinfunction "6_6") (pintype "passive"))
      (node (ref "X7") (pin "1") (pinfunction "1_1") (pintype "passive"))
      (node (ref "X8") (pin "1") (pinfunction "1_1") (pintype "passive"))
    )
    (net (code "39") (name "GND_CAN") (class "Default")
      (node (ref "C70") (pin "2") (pinfunction "2_2") (pintype "passive"))
      (node (ref "C75") (pin "1") (pinfunction "1_1") (pintype "passive"))
      (node (ref "C78") (pin "1") (pinfunction "1_1") (pintype "passive"))
      (node (ref "C79") (pin "1") (pinfunction "1_1") (pintype "passive"))
      (node (ref "DA10") (pin "3") (pintype "passive"))
      (node (ref "DD5") (pin "3") (pinfunction "Vout-_3") (pintype "passive"))
      (node (ref "DD6") (pin "10") (pinfunction "GND2_10") (pintype "passive"))
      (node (ref "DD6") (pin "15") (pinfunction "GND2_15") (pintype "passive"))
      (node (ref "DD6") (pin "9") (pinfunction "GND2_9") (pintype "passive"))
      (node (ref "X8") (pin "2") (pinfunction "2_2") (pintype "passive"))
    )
    (net (code "40") (name "Net-(C67-Pad1)") (class "Default")
      (node (ref "C67") (pin "1") (pinfunction "1_1") (pintype "passive"))
      (node (ref "C68") (pin "2") (pinfunction "2_2") (pintype "passive"))
      (node (ref "R63") (pin "2") (pinfunction "2_2") (pintype "passive"))
      (node (ref "R64") (pin "1") (pinfunction "1_1") (pintype "passive"))
    )
    (net (code "41") (name "Net-(C68-Pad1)") (class "Default")
      (node (ref "C68") (pin "1") (pinfunction "1_1") (pintype "passive"))
      (node (ref "C73") (pin "2") (pinfunction "2_2") (pintype "passive"))
      (node (ref "R67") (pin "2") (pinfunction "2_2") (pintype "passive"))
      (node (ref "R68") (pin "1") (pinfunction "1_1") (pintype "passive"))
    )
    (net (code "42") (name "Net-(C75-Pad2)") (class "Default")
      (node (ref "C75") (pin "2") (pinfunction "2_2") (pintype "passive"))
      (node (ref "R71") (pin "1") (pinfunction "1_1") (pintype "passive"))
      (node (ref "R72") (pin "2") (pinfunction "2_2") (pintype "passive"))
    )
    (net (code "43") (name "Net-(DA9-+IN)") (class "Default")
      (node (ref "C71") (pin "2") (pinfunction "2_2") (pintype "passive"))
      (node (ref "DA9") (pin "1") (pinfunction "+IN_1") (pintype "passive"))
      (node (ref "R68") (pin "2") (pinfunction "2_2") (pintype "passive"))
      (node (ref "R69") (pin "2") (pinfunction "2_2") (pintype "passive"))
    )
    (net (code "44") (name "Net-(DA9--IN)") (class "Default")
      (node (ref "C66") (pin "2") (pinfunction "2_2") (pintype "passive"))
      (node (ref "DA9") (pin "3") (pinfunction "-IN_3") (pintype "passive"))
      (node (ref "R64") (pin "2") (pinfunction "2_2") (pintype "passive"))
      (node (ref "R65") (pin "1") (pinfunction "1_1") (pintype "passive"))
    )
    (net (code "45") (name "Net-(DA9-OUT)") (class "Default")
      (node (ref "C66") (pin "1") (pinfunction "1_1") (pintype "passive"))
      (node (ref "DA9") (pin "4") (pinfunction "OUT_4") (pintype "passive"))
      (node (ref "R65") (pin "2") (pinfunction "2_2") (pintype "passive"))
      (node (ref "R66") (pin "1") (pinfunction "1_1") (pintype "passive"))
    )
    (net (code "46") (name "Net-(DD4-PH0_{slash}OSC_IN{slash}FT)") (class "Default")
      (node (ref "DD4") (pin "5") (pinfunction "PH0_/OSC_IN/FT_5") (pintype "passive"))
      (node (ref "G1") (pin "3") (pinfunction "DCLK_3") (pintype "power_in"))
    )
    (net (code "47") (name "Net-(DD4-VCAP_1)") (class "Default")
      (node (ref "C54") (pin "2") (pinfunction "2_2") (pintype "passive"))
      (node (ref "DD4") (pin "31") (pinfunction "VCAP_1_31") (pintype "passive"))
    )
    (net (code "48") (name "Net-(DD4-VCAP_2)") (class "Default")
      (node (ref "C53") (pin "2") (pinfunction "2_2") (pintype "passive"))
      (node (ref "DD4") (pin "47") (pinfunction "VCAP_2_47") (pintype "passive"))
    )
    (net (code "49") (name "Net-(DD4-VDDA)") (class "Default")
      (node (ref "C56") (pin "2") (pinfunction "2_2") (pintype "passive"))
      (node (ref "C57") (pin "1") (pinfunction "1_1") (pintype "passive"))
      (node (ref "DD4") (pin "13") (pinfunction "VDDA_13") (pintype "passive"))
      (node (ref "L3") (pin "1") (pinfunction "1_1") (pintype "passive"))
    )
    (net (code "50") (name "Net-(R51-Pad1)") (class "Default")
      (node (ref "R51") (pin "1") (pinfunction "1_1") (pintype "passive"))
      (node (ref "X4") (pin "3") (pinfunction "3_3") (pintype "passive"))
    )
    (net (code "51") (name "Net-(R52-Pad1)") (class "Default")
      (node (ref "R52") (pin "1") (pinfunction "1_1") (pintype "passive"))
      (node (ref "X4") (pin "4") (pinfunction "4_4") (pintype "passive"))
    )
    (net (code "52") (name "Net-(R53-Pad1)") (class "Default")
      (node (ref "R53") (pin "1") (pinfunction "1_1") (pintype "passive"))
      (node (ref "X4") (pin "5") (pinfunction "5_5") (pintype "passive"))
    )
    (net (code "53") (name "Net-(R54-Pad1)") (class "Default")
      (node (ref "R54") (pin "1") (pinfunction "1_1") (pintype "passive"))
      (node (ref "X4") (pin "6") (pinfunction "6_6") (pintype "passive"))
    )
    (net (code "54") (name "Net-(R55-Pad1)") (class "Default")
      (node (ref "R55") (pin "1") (pinfunction "1_1") (pintype "passive"))
      (node (ref "X4") (pin "7") (pinfunction "7_7") (pintype "passive"))
    )
    (net (code "55") (name "Net-(R56-Pad1)") (class "Default")
      (node (ref "R56") (pin "1") (pinfunction "1_1") (pintype "passive"))
      (node (ref "X4") (pin "8") (pinfunction "8_8") (pintype "passive"))
    )
    (net (code "56") (name "Net-(VD5-K)") (class "Default")
      (node (ref "VD5") (pin "1") (pinfunction "K_1") (pintype "passive"))
      (node (ref "X4") (pin "1") (pinfunction "1_1") (pintype "passive"))
      (node (ref "X4") (pin "2") (pinfunction "2_2") (pintype "passive"))
    )
    (net (code "57") (name "unconnected-(DD4-A15_{slash}_JTDI{slash}SPI3_NSS{slash}I2S3_WS{slash}TIM2_CH1_ETR{slash}_SPI1_NSS{slash}FT-Pad50)") (class "Default")
      (node (ref "DD4") (pin "50") (pinfunction "A15_/_JTDI/SPI3_NSS/I2S3_WS/TIM2_CH1_ETR/_SPI1_NSS/FT_50") (pintype "passive"))
    )
    (net (code "58") (name "unconnected-(DD4-PA2_{slash}_USART2_TX{slash}TIM5_CH3{slash}ADC123_IN2{slash}TIM9_CH1{slash}TIM2_CH3{slash}ADC123_IN2{slash}FT-Pad16)") (class "Default")
      (node (ref "DD4") (pin "16") (pinfunction "PA2_/_USART2_TX/TIM5_CH3/ADC123_IN2/TIM9_CH1/TIM2_CH3/ADC123_IN2/FT_16") (pintype "passive"))
    )
    (net (code "59") (name "unconnected-(DD4-PA3_{slash}_USART2_RX{slash}TIM5_CH4{slash}TIM9_CH2{slash}TIM2_CH4{slash}OTG_HS_ULPI_D0{slash}ETH_MII_COL{slash}ADC123_IN3{slash}FT-Pad17)") (class "Default")
      (node (ref "DD4") (pin "17") (pinfunction "PA3_/_USART2_RX/TIM5_CH4/TIM9_CH2/TIM2_CH4/OTG_HS_ULPI_D0/ETH_MII_COL/ADC123_IN3/FT_17") (pintype "passive"))
    )
    (net (code "60") (name "unconnected-(DD4-PA4_{slash}_SPI1_NSS{slash}SPI3_NSS{slash}USART2_CK{slash}DCMI_HSYNC{slash}OTG_HS_SOF{slash}I2S3_WS{slash}ADC12_IN4{slash}DAC_OUT1{slash}TTa-Pad20)") (class "Default")
      (node (ref "DD4") (pin "20") (pinfunction "PA4_/_SPI1_NSS/SPI3_NSS/USART2_CK/DCMI_HSYNC/OTG_HS_SOF/I2S3_WS/ADC12_IN4/DAC_OUT1/TTa_20") (pintype "passive"))
    )
    (net (code "61") (name "unconnected-(DD4-PA5_{slash}_SPI1_SCK{slash}OTG_HS_ULPI_CK{slash}TIM2_CH1_ETR{slash}TIM8_CH1N{slash}ADC12_IN5{slash}DAC_OUT2{slash}TTa-Pad21)") (class "Default")
      (node (ref "DD4") (pin "21") (pinfunction "PA5_/_SPI1_SCK/OTG_HS_ULPI_CK/TIM2_CH1_ETR/TIM8_CH1N/ADC12_IN5/DAC_OUT2/TTa_21") (pintype "passive"))
    )
    (net (code "62") (name "unconnected-(DD4-PA6_{slash}_SPI1_MISO{slash}TIM8_BKIN{slash}TIM13_CH1{slash}DCMI_PIXCLK{slash}TIM3_CH1{slash}TIM1_BKIN{slash}ADC12_IN6{slash}FT-Pad22)") (class "Default")
      (node (ref "DD4") (pin "22") (pinfunction "PA6_/_SPI1_MISO/TIM8_BKIN/TIM13_CH1/DCMI_PIXCLK/TIM3_CH1/TIM1_BKIN/ADC12_IN6/FT_22") (pintype "passive"))
    )
    (net (code "63") (name "unconnected-(DD4-PA7_{slash}_SPI1_MOSI{slash}TIM8_CH1N{slash}TIM14_CH1{slash}TIM3_CH2{slash}ETH_MII_RX_DV{slash}TIM1_CH1N{slash}ETH_RMII_CRS_DV{slash}ADC12_IN7{slash}FT-Pad23)") (class "Default")
      (node (ref "DD4") (pin "23") (pinfunction "PA7_/_SPI1_MOSI/TIM8_CH1N/TIM14_CH1/TIM3_CH2/ETH_MII_RX_DV/TIM1_CH1N/ETH_RMII_CRS_DV/ADC12_IN7/FT_23") (pintype "passive"))
    )
    (net (code "64") (name "unconnected-(DD4-PB0_{slash}_TIM3_CH3{slash}TIM8_CH2N{slash}OTG_HS_ULPI_D1{slash}ETH_MII_RXD2{slash}TIM1_CH2N{slash}ADC12_IN8{slash}FT-Pad26)") (class "Default")
      (node (ref "DD4") (pin "26") (pinfunction "PB0_/_TIM3_CH3/TIM8_CH2N/OTG_HS_ULPI_D1/ETH_MII_RXD2/TIM1_CH2N/ADC12_IN8/FT_26") (pintype "passive"))
    )
    (net (code "65") (name "unconnected-(DD4-PB2_{slash}_BOOT1{slash}FT-Pad28)") (class "Default")
      (node (ref "DD4") (pin "28") (pinfunction "PB2_/_BOOT1/FT_28") (pintype "passive"))
    )
    (net (code "66") (name "unconnected-(DD4-PB4_{slash}_NJTRST{slash}SPI3_MISO{slash}TIM3_CH1{slash}SPI1_MISO{slash}I2S3ext_SD{slash}FT-Pad56)") (class "Default")
      (node (ref "DD4") (pin "56") (pinfunction "PB4_/_NJTRST/SPI3_MISO/TIM3_CH1/SPI1_MISO/I2S3ext_SD/FT_56") (pintype "passive"))
    )
    (net (code "67") (name "unconnected-(DD4-PB5_{slash}_I2C1_SMBA{slash}CAN2_RX{slash}OTG_HS_ULPI_D7{slash}ETH_PPS_OUT{slash}TIM3_CH2{slash}SPI1_MOSI{slash}SPI3_MOSI{slash}DCMI_D10{slash}I2S3_SD{slash}FT-Pad57)") (class "Default")
      (node (ref "DD4") (pin "57") (pinfunction "PB5_/_I2C1_SMBA/CAN2_RX/OTG_HS_ULPI_D7/ETH_PPS_OUT/TIM3_CH2/SPI1_MOSI/SPI3_MOSI/DCMI_D10/I2S3_SD/FT_57") (pintype "passive"))
    )
    (net (code "68") (name "unconnected-(DD4-PB8_{slash}_TIM4_CH3{slash}SDIO_D4{slash}TIM10_CH1{slash}DCMI_D6{slash}ETH_MII_TXD3{slash}I2C1_SCL{slash}CAN1_RX{slash}FT-Pad61)") (class "Default")
      (node (ref "DD4") (pin "61") (pinfunction "PB8_/_TIM4_CH3/SDIO_D4/TIM10_CH1/DCMI_D6/ETH_MII_TXD3/I2C1_SCL/CAN1_RX/FT_61") (pintype "passive"))
    )
    (net (code "69") (name "unconnected-(DD4-PB9_{slash}_SPI2_NSS{slash}I2S2_WS{slash}TIM4_CH4{slash}TIM11_CH1{slash}SDIO_D5{slash}DCMI_D7{slash}I2C1_SDA{slash}CAN1_TX{slash}FT-Pad62)") (class "Default")
      (node (ref "DD4") (pin "62") (pinfunction "PB9_/_SPI2_NSS/I2S2_WS/TIM4_CH4/TIM11_CH1/SDIO_D5/DCMI_D7/I2C1_SDA/CAN1_TX/FT_62") (pintype "passive"))
    )
    (net (code "70") (name "unconnected-(DD4-PC2_{slash}_SPI2_MISO{slash}OTG_HS_ULPI_DIR{slash}ETH_MII_TXD2{slash}I2S2ext_SD{slash}ADC123_IN12{slash}FT-Pad10)") (class "Default")
      (node (ref "DD4") (pin "10") (pinfunction "PC2_/_SPI2_MISO/OTG_HS_ULPI_DIR/ETH_MII_TXD2/I2S2ext_SD/ADC123_IN12/FT_10") (pintype "passive"))
    )
    (net (code "71") (name "unconnected-(DD4-PC3_{slash}_SPI2_MOSI{slash}I2S2_SD{slash}OTG_HS_ULPI_NXT{slash}ETH_MII_TX_CLK{slash}ADC123_IN13{slash}FT-Pad11)") (class "Default")
      (node (ref "DD4") (pin "11") (pinfunction "PC3_/_SPI2_MOSI/I2S2_SD/OTG_HS_ULPI_NXT/ETH_MII_TX_CLK/ADC123_IN13/FT_11") (pintype "passive"))
    )
    (net (code "72") (name "unconnected-(DD4-PC4_{slash}_ETH_RMII_RX_D0{slash}ETH_MII_RX_D0{slash}ADC12_IN14{slash}FT-Pad24)") (class "Default")
      (node (ref "DD4") (pin "24") (pinfunction "PC4_/_ETH_RMII_RX_D0/ETH_MII_RX_D0/ADC12_IN14/FT_24") (pintype "passive"))
    )
    (net (code "73") (name "unconnected-(DD4-PC5_{slash}_ETH_RMII_RX_D1{slash}ETH_MII_RX_D1{slash}ADC12_IN15{slash}FT-Pad25)") (class "Default")
      (node (ref "DD4") (pin "25") (pinfunction "PC5_/_ETH_RMII_RX_D1/ETH_MII_RX_D1/ADC12_IN15/FT_25") (pintype "passive"))
    )
    (net (code "74") (name "unconnected-(DD4-PC6_{slash}_I2S2_MCK{slash}TIM8_CH1{slash}SDIO_D6{slash}USART6_TX{slash}DCMI_D0{slash}TIM3_CH1{slash}FT-Pad37)") (class "Default")
      (node (ref "DD4") (pin "37") (pinfunction "PC6_/_I2S2_MCK/TIM8_CH1/SDIO_D6/USART6_TX/DCMI_D0/TIM3_CH1/FT_37") (pintype "passive"))
    )
    (net (code "75") (name "unconnected-(DD4-PC9_{slash}_I2S_CKIN{slash}MCO2{slash}TIM8_CH4{slash}SDIO_D1{slash}I2C3_SDA{slash}DCMI_D3{slash}TIM3_CH4{slash}FT-Pad40)") (class "Default")
      (node (ref "DD4") (pin "40") (pinfunction "PC9_/_I2S_CKIN/MCO2/TIM8_CH4/SDIO_D1/I2C3_SDA/DCMI_D3/TIM3_CH4/FT_40") (pintype "passive"))
    )
    (net (code "76") (name "unconnected-(DD4-PC10_{slash}_SPI3_SCK{slash}I2S3_CK{slash}UART4_TX{slash}SDIO_D2{slash}DCMI_D8{slash}USART3_TX{slash}FT-Pad51)") (class "Default")
      (node (ref "DD4") (pin "51") (pinfunction "PC10_/_SPI3_SCK/I2S3_CK/UART4_TX/SDIO_D2/DCMI_D8/USART3_TX/FT_51") (pintype "passive"))
    )
    (net (code "77") (name "unconnected-(DD4-PC11_{slash}_UART4_RX{slash}SPI3_MISO{slash}SDIO_D3{slash}DCMI_D4{slash}USART3_RX{slash}I2S3ext_SD{slash}FT-Pad52)") (class "Default")
      (node (ref "DD4") (pin "52") (pinfunction "PC11_/_UART4_RX/SPI3_MISO/SDIO_D3/DCMI_D4/USART3_RX/I2S3ext_SD/FT_52") (pintype "passive"))
    )
    (net (code "78") (name "unconnected-(DD4-PC12_{slash}_UART5_TX{slash}SDIO_CK{slash}DCMI_D9{slash}SPI3_MOSI{slash}I2S3_SD{slash}USART3_CK{slash}FT-Pad53)") (class "Default")
      (node (ref "DD4") (pin "53") (pinfunction "PC12_/_UART5_TX/SDIO_CK/DCMI_D9/SPI3_MOSI/I2S3_SD/USART3_CK/FT_53") (pintype "passive"))
    )
    (net (code "79") (name "unconnected-(DD4-PC13_{slash}_EVENTOUT{slash}RTC_OUT{slash}RTC_TAMP1{slash}RTC_TS{slash}FT-Pad2)") (class "Default")
      (node (ref "DD4") (pin "2") (pinfunction "PC13_/_EVENTOUT/RTC_OUT/RTC_TAMP1/RTC_TS/FT_2") (pintype "passive"))
    )
    (net (code "80") (name "unconnected-(DD4-PC14_{slash}_OSC32_IN{slash}FT-Pad3)") (class "Default")
      (node (ref "DD4") (pin "3") (pinfunction "PC14_/_OSC32_IN/FT_3") (pintype "passive"))
    )
    (net (code "81") (name "unconnected-(DD4-PC15_{slash}_OSC32_OUT{slash}FT-Pad4)") (class "Default")
      (node (ref "DD4") (pin "4") (pinfunction "PC15_/_OSC32_OUT/FT_4") (pintype "passive"))
    )
    (net (code "82") (name "unconnected-(DD4-PD2_{slash}_TIM3_ETR{slash}UART5_RX{slash}SDIO_CMD{slash}DCMI_D11{slash}FT-Pad54)") (class "Default")
      (node (ref "DD4") (pin "54") (pinfunction "PD2_/_TIM3_ETR/UART5_RX/SDIO_CMD/DCMI_D11/FT_54") (pintype "passive"))
    )
    (net (code "83") (name "unconnected-(DD4-PH1_{slash}OSC_OUT{slash}FT-Pad6)") (class "Default")
      (node (ref "DD4") (pin "6") (pinfunction "PH1_/OSC_OUT/FT_6") (pintype "passive+no_connect"))
    )
    (net (code "84") (name "unconnected-(DD6-NC-Pad4)") (class "Default")
      (node (ref "DD6") (pin "4") (pinfunction "NC_4") (pintype "passive+no_connect"))
    )
    (net (code "85") (name "unconnected-(DD6-NC-Pad5)") (class "Default")
      (node (ref "DD6") (pin "5") (pinfunction "NC_5") (pintype "passive+no_connect"))
    )
    (net (code "86") (name "unconnected-(DD6-NC-Pad11)") (class "Default")
      (node (ref "DD6") (pin "11") (pinfunction "NC_11") (pintype "passive+no_connect"))
    )
    (net (code "87") (name "unconnected-(DD6-NC-Pad14)") (class "Default")
      (node (ref "DD6") (pin "14") (pinfunction "NC_14") (pintype "passive+no_connect"))
    )
    (net (code "88") (name "unconnected-(G1-NC-Pad1)") (class "Default")
      (node (ref "G1") (pin "1") (pinfunction "NC_1") (pintype "power_in+no_connect"))
    )
  )
)
